# Debugger.net
KiCad netlist of a schematic drawn in Altium Designer
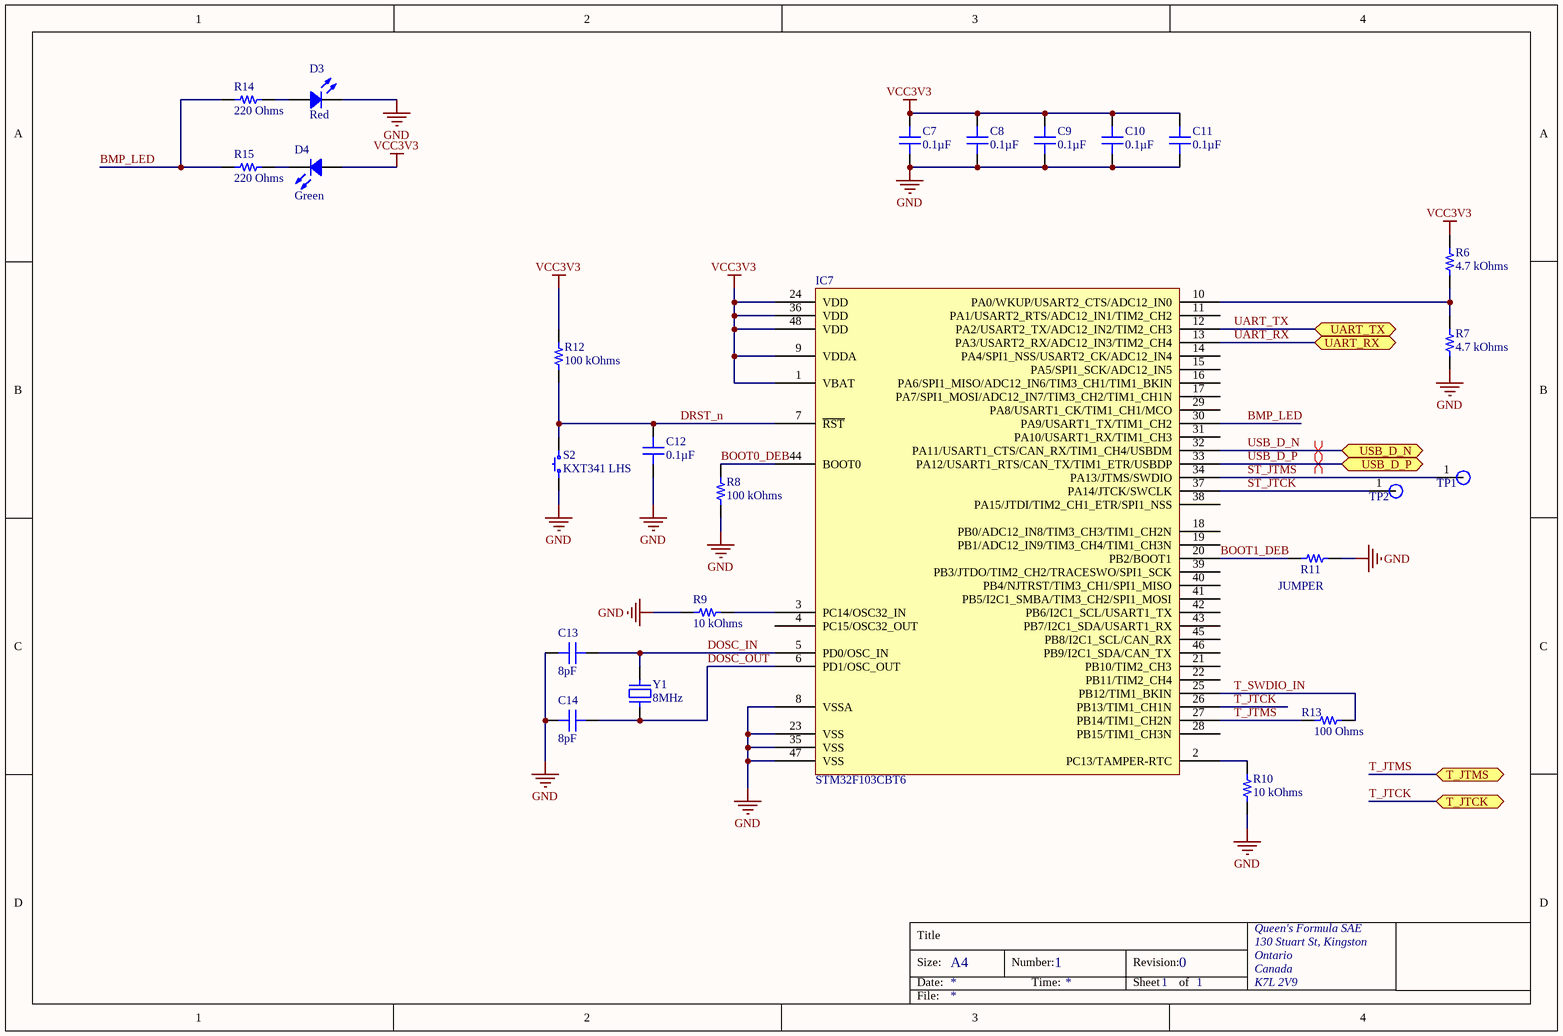
[diagram p0: Debugger.SchDoc]

(export (version "E")
  (design (tool "Eeschema 10.0.6"))
  (components
    (comp (ref "C7")
      (value "0.1µF")
      (footprint "CAP 0201_0603")
      (description "CAP CER 0.1UF 16V X5R 0201")
      (fields (field (name "PART NUMBER") "EMK063BJ104KP-F") (field (name "MANUFACTURER") "Taiyo Yuden"))
      (libsource (lib "Celestial") (part "Capacitor"))
    )
    (comp (ref "C8")
      (value "0.1µF")
      (footprint "CAP 0201_0603")
      (description "CAP CER 0.1UF 16V X5R 0201")
      (fields (field (name "PART NUMBER") "EMK063BJ104KP-F") (field (name "MANUFACTURER") "Taiyo Yuden"))
      (libsource (lib "Celestial") (part "Capacitor"))
    )
    (comp (ref "C9")
      (value "0.1µF")
      (footprint "CAP 0201_0603")
      (description "CAP CER 0.1UF 16V X5R 0201")
      (fields (field (name "PART NUMBER") "EMK063BJ104KP-F") (field (name "MANUFACTURER") "Taiyo Yuden"))
      (libsource (lib "Celestial") (part "Capacitor"))
    )
    (comp (ref "C10")
      (value "0.1µF")
      (footprint "CAP 0201_0603")
      (description "CAP CER 0.1UF 16V X5R 0201")
      (fields (field (name "PART NUMBER") "EMK063BJ104KP-F") (field (name "MANUFACTURER") "Taiyo Yuden"))
      (libsource (lib "Celestial") (part "Capacitor"))
    )
    (comp (ref "C11")
      (value "0.1µF")
      (footprint "CAP 0201_0603")
      (description "CAP CER 0.1UF 16V X5R 0201")
      (fields (field (name "PART NUMBER") "EMK063BJ104KP-F") (field (name "MANUFACTURER") "Taiyo Yuden"))
      (libsource (lib "Celestial") (part "Capacitor"))
    )
    (comp (ref "C12")
      (value "0.1µF")
      (footprint "CAP 0201_0603")
      (description "CAP CER 0.1UF 16V X5R 0201")
      (fields (field (name "PART NUMBER") "EMK063BJ104KP-F") (field (name "MANUFACTURER") "Taiyo Yuden"))
      (libsource (lib "Celestial") (part "Capacitor"))
    )
    (comp (ref "C13")
      (value "8pF")
      (footprint "CAP 0402_1005")
      (description "CAP CER 8PF 50V NP0 0402")
      (fields
        (field (name "PART NUMBER") "C1005NP01H080D050BA")
        (field (name "MANUFACTURER") "TDK Corporation")
      )
      (libsource (lib "Celestial") (part "Capacitor"))
    )
    (comp (ref "C14")
      (value "8pF")
      (footprint "CAP 0402_1005")
      (description "CAP CER 8PF 50V NP0 0402")
      (fields
        (field (name "PART NUMBER") "C1005NP01H080D050BA")
        (field (name "MANUFACTURER") "TDK Corporation")
      )
      (libsource (lib "Celestial") (part "Capacitor"))
    )
    (comp (ref "D3")
      (value "Red")
      (footprint "LED 0402_1005 RED")
      (description "LED RED CLEAR CHIP SMD")
      (fields (field (name "PART NUMBER") "APG1005SEC/E-T") (field (name "MANUFACTURER") "Kingbright"))
      (libsource (lib "Celestial") (part "LED"))
    )
    (comp (ref "D4")
      (value "Green")
      (footprint "LED 0402_1005 GREEN")
      (description "LED GREEN CLEAR 2SMD")
      (fields (field (name "PART NUMBER") "APHHS1005LCGCK") (field (name "MANUFACTURER") "Kingbright"))
      (libsource (lib "Celestial") (part "LED"))
    )
    (comp (ref "IC7")
      (value "STM32F103CBT6")
      (footprint "ST LQFP-48 7X7MM")
      (description "IC MCU 32BIT 128KB FLASH 48LQFP")
      (fields (field (name "MANUFACTURER") "STMicroelectronics"))
      (libsource (lib "Celestial") (part "ST STM32F103 48PIN"))
    )
    (comp (ref "R6")
      (value "4.7 kOhms")
      (footprint "RES 0402_1005")
      (description "RES SMD 4.7K OHM 1% 1/16W 0402")
      (fields (field (name "PART NUMBER") "AC0402FR-074K7L") (field (name "MANUFACTURER") "Yageo"))
      (libsource (lib "Celestial") (part "Resistor"))
    )
    (comp (ref "R7")
      (value "4.7 kOhms")
      (footprint "RES 0402_1005")
      (description "RES SMD 4.7K OHM 1% 1/16W 0402")
      (fields (field (name "PART NUMBER") "AC0402FR-074K7L") (field (name "MANUFACTURER") "Yageo"))
      (libsource (lib "Celestial") (part "Resistor"))
    )
    (comp (ref "R8")
      (value "100 kOhms")
      (footprint "RES 0402_1005")
      (description "RES SMD 100K OHM 1% 1/16W 0402")
      (fields (field (name "PART NUMBER") "AC0402FR-07100KL") (field (name "MANUFACTURER") "Yageo"))
      (libsource (lib "Celestial") (part "Resistor"))
    )
    (comp (ref "R9")
      (value "10 kOhms")
      (footprint "RES 0402_1005")
      (description "RES SMD 10K OHM 1% 1/16W 0402")
      (fields (field (name "PART NUMBER") "AC0402FR-0710KL") (field (name "MANUFACTURER") "Yageo"))
      (libsource (lib "Celestial") (part "Resistor"))
    )
    (comp (ref "R10")
      (value "10 kOhms")
      (footprint "RES 0402_1005")
      (description "RES SMD 10K OHM 1% 1/16W 0402")
      (fields (field (name "PART NUMBER") "AC0402FR-0710KL") (field (name "MANUFACTURER") "Yageo"))
      (libsource (lib "Celestial") (part "Resistor"))
    )
    (comp (ref "R11")
      (value "JUMPER")
      (footprint "RES 0402_1005")
      (description "0402 JUMPER ON TAPE AND REEL")
      (fields (field (name "PART NUMBER") "5113") (field (name "MANUFACTURER") "Keystone Electronics"))
      (libsource (lib "Celestial") (part "Resistor"))
    )
    (comp (ref "R12")
      (value "100 kOhms")
      (footprint "RES 0201_0603")
      (description "RES SMD 100K OHM 1% 1/20W 0201")
      (fields
        (field (name "PART NUMBER") "CRG0201F100K")
        (field (name "MANUFACTURER") "TE Connectivity Passive Product")
      )
      (libsource (lib "Celestial") (part "Resistor"))
    )
    (comp (ref "R13")
      (value "100 Ohms")
      (footprint "RES 0201_0603")
      (description "RES SMD 100 OHM 1% 1/20W 0201")
      (fields (field (name "PART NUMBER") "CRCW0201100RFKED") (field (name "MANUFACTURER") "Vishay Dale"))
      (libsource (lib "Celestial") (part "Resistor"))
    )
    (comp (ref "R14")
      (value "220 Ohms")
      (footprint "RES 0201_0603")
      (description "RES 220 OHM 1% 1/20W 0201")
      (fields
        (field (name "PART NUMBER") "RK73H1HTTC2200F")
        (field (name "MANUFACTURER") "KOA Speer Electronics, Inc.")
      )
      (libsource (lib "Celestial") (part "Resistor"))
    )
    (comp (ref "R15")
      (value "220 Ohms")
      (footprint "RES 0201_0603")
      (description "RES 220 OHM 1% 1/20W 0201")
      (fields
        (field (name "PART NUMBER") "RK73H1HTTC2200F")
        (field (name "MANUFACTURER") "KOA Speer Electronics, Inc.")
      )
      (libsource (lib "Celestial") (part "Resistor"))
    )
    (comp (ref "S2")
      (value "KXT341 LHS")
      (footprint "C&K KXT3")
      (description "SWITCH TACTILE SPST-NO 0.02A 15V")
      (fields (field (name "MANUFACTURER") "C&K"))
      (libsource (lib "Celestial") (part "SPST-NO 2 PIN"))
    )
    (comp (ref "TP1") (value "Test Point") (footprint "ethan:TP1") (libsource (lib "ethan") (part "TP1")))
    (comp (ref "TP2") (value "Test Point") (footprint "ethan:TP1") (libsource (lib "ethan") (part "TP1")))
    (comp (ref "Y1")
      (value "8MHz")
      (footprint "NDK NX3225GD")
      (description "CRYSTAL 8.0000MHZ 8PF SMD")
      (fields
        (field (name "PART NUMBER") "NX3225GD-8MHZ-STD-CRA-3")
        (field (name "MANUFACTURER") "NDK America, Inc.")
      )
      (libsource (lib "Celestial") (part "NDK NX3225GD"))
    )
  )
  (nets
    (net (code "1") (name "/BMP_LED") (class "Default")
      (node (ref "IC7") (pin "30") (pinfunction "PA9/USART1_TX/TIM1_CH2_30") (pintype "passive"))
      (node (ref "R14") (pin "2") (pinfunction "2_2") (pintype "passive"))
      (node (ref "R15") (pin "2") (pinfunction "2_2") (pintype "passive"))
    )
    (net (code "2") (name "/BOOT0_DEB") (class "Default")
      (node (ref "IC7") (pin "44") (pinfunction "BOOT0_44") (pintype "passive"))
      (node (ref "R8") (pin "2") (pinfunction "2_2") (pintype "passive"))
    )
    (net (code "3") (name "/BOOT1_DEB") (class "Default")
      (node (ref "IC7") (pin "20") (pinfunction "PB2/BOOT1_20") (pintype "passive"))
      (node (ref "R11") (pin "2") (pinfunction "2_2") (pintype "passive"))
    )
    (net (code "4") (name "/DOSC_IN") (class "Default")
      (node (ref "C13") (pin "2") (pinfunction "2_2") (pintype "passive"))
      (node (ref "IC7") (pin "5") (pinfunction "PD0/OSC_IN_5") (pintype "passive"))
      (node (ref "Y1") (pin "2") (pinfunction "2_2") (pintype "passive"))
    )
    (net (code "5") (name "/DOSC_OUT") (class "Default")
      (node (ref "C14") (pin "2") (pinfunction "2_2") (pintype "passive"))
      (node (ref "IC7") (pin "6") (pinfunction "PD1/OSC_OUT_6") (pintype "passive"))
      (node (ref "Y1") (pin "1") (pinfunction "1_1") (pintype "passive"))
    )
    (net (code "6") (name "/DRST_n") (class "Default")
      (node (ref "C12") (pin "2") (pinfunction "2_2") (pintype "passive"))
      (node (ref "IC7") (pin "7") (pinfunction "~{RST}_7") (pintype "passive"))
      (node (ref "R12") (pin "1") (pinfunction "1_1") (pintype "passive"))
      (node (ref "S2") (pin "2") (pinfunction "2_2") (pintype "passive"))
    )
    (net (code "7") (name "/ST_JTCK") (class "Default")
      (node (ref "IC7") (pin "37") (pinfunction "PA14/JTCK/SWCLK_37") (pintype "passive"))
      (node (ref "TP2") (pin "1") (pinfunction "1_1") (pintype "passive"))
    )
    (net (code "8") (name "/ST_JTMS") (class "Default")
      (node (ref "IC7") (pin "34") (pinfunction "PA13/JTMS/SWDIO_34") (pintype "passive"))
      (node (ref "TP1") (pin "1") (pinfunction "1_1") (pintype "passive"))
    )
    (net (code "9") (name "/T_JTCK") (class "Default")
      (node (ref "IC7") (pin "26") (pinfunction "PB13/TIM1_CH1N_26") (pintype "passive"))
    )
    (net (code "10") (name "/T_JTMS") (class "Default")
      (node (ref "IC7") (pin "27") (pinfunction "PB14/TIM1_CH2N_27") (pintype "passive"))
      (node (ref "R13") (pin "1") (pinfunction "1_1") (pintype "passive"))
    )
    (net (code "11") (name "/T_SWDIO_IN") (class "Default")
      (node (ref "IC7") (pin "25") (pinfunction "PB12/TIM1_BKIN_25") (pintype "passive"))
      (node (ref "R13") (pin "2") (pinfunction "2_2") (pintype "passive"))
    )
    (net (code "12") (name "/UART_RX") (class "Default")
      (node (ref "IC7") (pin "13") (pinfunction "PA3/USART2_RX/ADC12_IN3/TIM2_CH4_13") (pintype "passive"))
    )
    (net (code "13") (name "/UART_TX") (class "Default")
      (node (ref "IC7") (pin "12") (pinfunction "PA2/USART2_TX/ADC12_IN2/TIM2_CH3_12") (pintype "passive"))
    )
    (net (code "14") (name "/USB_D_N") (class "Default")
      (node (ref "IC7") (pin "32") (pinfunction "PA11/USART1_CTS/CAN_RX/TIM1_CH4/USBDM_32") (pintype "passive"))
    )
    (net (code "15") (name "/USB_D_P") (class "Default")
      (node (ref "IC7") (pin "33") (pinfunction "PA12/USART1_RTS/CAN_TX/TIM1_ETR/USBDP_33") (pintype "passive"))
    )
    (net (code "16") (name "GND") (class "Default")
      (node (ref "C10") (pin "1") (pinfunction "1_1") (pintype "passive"))
      (node (ref "C11") (pin "1") (pinfunction "1_1") (pintype "passive"))
      (node (ref "C12") (pin "1") (pinfunction "1_1") (pintype "passive"))
      (node (ref "C13") (pin "1") (pinfunction "1_1") (pintype "passive"))
      (node (ref "C14") (pin "1") (pinfunction "1_1") (pintype "passive"))
      (node (ref "C7") (pin "1") (pinfunction "1_1") (pintype "passive"))
      (node (ref "C8") (pin "1") (pinfunction "1_1") (pintype "passive"))
      (node (ref "C9") (pin "1") (pinfunction "1_1") (pintype "passive"))
      (node (ref "D3") (pin "2") (pinfunction "2_2") (pintype "passive"))
      (node (ref "IC7") (pin "23") (pinfunction "VSS_23") (pintype "passive"))
      (node (ref "IC7") (pin "35") (pinfunction "VSS_35") (pintype "passive"))
      (node (ref "IC7") (pin "47") (pinfunction "VSS_47") (pintype "passive"))
      (node (ref "IC7") (pin "8") (pinfunction "VSSA_8") (pintype "passive"))
      (node (ref "R10") (pin "1") (pinfunction "1_1") (pintype "passive"))
      (node (ref "R11") (pin "1") (pinfunction "1_1") (pintype "passive"))
      (node (ref "R7") (pin "1") (pinfunction "1_1") (pintype "passive"))
      (node (ref "R8") (pin "1") (pinfunction "1_1") (pintype "passive"))
      (node (ref "R9") (pin "2") (pinfunction "2_2") (pintype "passive"))
      (node (ref "S2") (pin "1") (pinfunction "1_1") (pintype "passive"))
    )
    (net (code "17") (name "Net-(D3-Pad1)") (class "Default")
      (node (ref "D3") (pin "1") (pinfunction "1_1") (pintype "passive"))
      (node (ref "R14") (pin "1") (pinfunction "1_1") (pintype "passive"))
    )
    (net (code "18") (name "Net-(D4-Pad2)") (class "Default")
      (node (ref "D4") (pin "2") (pinfunction "2_2") (pintype "passive"))
      (node (ref "R15") (pin "1") (pinfunction "1_1") (pintype "passive"))
    )
    (net (code "19") (name "Net-(IC7-PA0{slash}WKUP{slash}USART2_CTS{slash}ADC12_IN0)") (class "Default")
      (node (ref "IC7") (pin "10") (pinfunction "PA0/WKUP/USART2_CTS/ADC12_IN0_10") (pintype "passive"))
      (node (ref "R6") (pin "1") (pinfunction "1_1") (pintype "passive"))
      (node (ref "R7") (pin "2") (pinfunction "2_2") (pintype "passive"))
    )
    (net (code "20") (name "Net-(IC7-PC13{slash}TAMPER-RTC)") (class "Default")
      (node (ref "IC7") (pin "2") (pinfunction "PC13/TAMPER-RTC_2") (pintype "passive"))
      (node (ref "R10") (pin "2") (pinfunction "2_2") (pintype "passive"))
    )
    (net (code "21") (name "Net-(IC7-PC14{slash}OSC32_IN)") (class "Default")
      (node (ref "IC7") (pin "3") (pinfunction "PC14/OSC32_IN_3") (pintype "passive"))
      (node (ref "R9") (pin "1") (pinfunction "1_1") (pintype "passive"))
    )
    (net (code "22") (name "VCC3V3") (class "Default")
      (node (ref "C10") (pin "2") (pinfunction "2_2") (pintype "passive"))
      (node (ref "C11") (pin "2") (pinfunction "2_2") (pintype "passive"))
      (node (ref "C7") (pin "2") (pinfunction "2_2") (pintype "passive"))
      (node (ref "C8") (pin "2") (pinfunction "2_2") (pintype "passive"))
      (node (ref "C9") (pin "2") (pinfunction "2_2") (pintype "passive"))
      (node (ref "D4") (pin "1") (pinfunction "1_1") (pintype "passive"))
      (node (ref "IC7") (pin "1") (pinfunction "VBAT_1") (pintype "passive"))
      (node (ref "IC7") (pin "24") (pinfunction "VDD_24") (pintype "passive"))
      (node (ref "IC7") (pin "36") (pinfunction "VDD_36") (pintype "passive"))
      (node (ref "IC7") (pin "48") (pinfunction "VDD_48") (pintype "passive"))
      (node (ref "IC7") (pin "9") (pinfunction "VDDA_9") (pintype "passive"))
      (node (ref "R12") (pin "2") (pinfunction "2_2") (pintype "passive"))
      (node (ref "R6") (pin "2") (pinfunction "2_2") (pintype "passive"))
    )
    (net (code "23") (name "unconnected-(IC7-PA1{slash}USART2_RTS{slash}ADC12_IN1{slash}TIM2_CH2-Pad11)") (class "Default")
      (node (ref "IC7") (pin "11") (pinfunction "PA1/USART2_RTS/ADC12_IN1/TIM2_CH2_11") (pintype "passive"))
    )
    (net (code "24") (name "unconnected-(IC7-PA4{slash}SPI1_NSS{slash}USART2_CK{slash}ADC12_IN4-Pad14)") (class "Default")
      (node (ref "IC7") (pin "14") (pinfunction "PA4/SPI1_NSS/USART2_CK/ADC12_IN4_14") (pintype "passive"))
    )
    (net (code "25") (name "unconnected-(IC7-PA5{slash}SPI1_SCK{slash}ADC12_IN5-Pad15)") (class "Default")
      (node (ref "IC7") (pin "15") (pinfunction "PA5/SPI1_SCK/ADC12_IN5_15") (pintype "passive"))
    )
    (net (code "26") (name "unconnected-(IC7-PA6{slash}SPI1_MISO{slash}ADC12_IN6{slash}TIM3_CH1{slash}TIM1_BKIN-Pad16)") (class "Default")
      (node (ref "IC7") (pin "16") (pinfunction "PA6/SPI1_MISO/ADC12_IN6/TIM3_CH1/TIM1_BKIN_16") (pintype "passive"))
    )
    (net (code "27") (name "unconnected-(IC7-PA7{slash}SPI1_MOSI{slash}ADC12_IN7{slash}TIM3_CH2{slash}TIM1_CH1N-Pad17)") (class "Default")
      (node (ref "IC7") (pin "17") (pinfunction "PA7/SPI1_MOSI/ADC12_IN7/TIM3_CH2/TIM1_CH1N_17") (pintype "passive"))
    )
    (net (code "28") (name "unconnected-(IC7-PA8{slash}USART1_CK{slash}TIM1_CH1{slash}MCO-Pad29)") (class "Default")
      (node (ref "IC7") (pin "29") (pinfunction "PA8/USART1_CK/TIM1_CH1/MCO_29") (pintype "passive"))
    )
    (net (code "29") (name "unconnected-(IC7-PA10{slash}USART1_RX{slash}TIM1_CH3-Pad31)") (class "Default")
      (node (ref "IC7") (pin "31") (pinfunction "PA10/USART1_RX/TIM1_CH3_31") (pintype "passive"))
    )
    (net (code "30") (name "unconnected-(IC7-PA15{slash}JTDI{slash}TIM2_CH1_ETR{slash}SPI1_NSS-Pad38)") (class "Default")
      (node (ref "IC7") (pin "38") (pinfunction "PA15/JTDI/TIM2_CH1_ETR/SPI1_NSS_38") (pintype "passive"))
    )
    (net (code "31") (name "unconnected-(IC7-PB0{slash}ADC12_IN8{slash}TIM3_CH3{slash}TIM1_CH2N-Pad18)") (class "Default")
      (node (ref "IC7") (pin "18") (pinfunction "PB0/ADC12_IN8/TIM3_CH3/TIM1_CH2N_18") (pintype "passive"))
    )
    (net (code "32") (name "unconnected-(IC7-PB1{slash}ADC12_IN9{slash}TIM3_CH4{slash}TIM1_CH3N-Pad19)") (class "Default")
      (node (ref "IC7") (pin "19") (pinfunction "PB1/ADC12_IN9/TIM3_CH4/TIM1_CH3N_19") (pintype "passive"))
    )
    (net (code "33") (name "unconnected-(IC7-PB3{slash}JTDO{slash}TIM2_CH2{slash}TRACESWO{slash}SPI1_SCK-Pad39)") (class "Default")
      (node (ref "IC7") (pin "39") (pinfunction "PB3/JTDO/TIM2_CH2/TRACESWO/SPI1_SCK_39") (pintype "passive"))
    )
    (net (code "34") (name "unconnected-(IC7-PB4{slash}NJTRST{slash}TIM3_CH1{slash}SPI1_MISO-Pad40)") (class "Default")
      (node (ref "IC7") (pin "40") (pinfunction "PB4/NJTRST/TIM3_CH1/SPI1_MISO_40") (pintype "passive"))
    )
    (net (code "35") (name "unconnected-(IC7-PB5{slash}I2C1_SMBA{slash}TIM3_CH2{slash}SPI1_MOSI-Pad41)") (class "Default")
      (node (ref "IC7") (pin "41") (pinfunction "PB5/I2C1_SMBA/TIM3_CH2/SPI1_MOSI_41") (pintype "passive"))
    )
    (net (code "36") (name "unconnected-(IC7-PB6{slash}I2C1_SCL{slash}USART1_TX-Pad42)") (class "Default")
      (node (ref "IC7") (pin "42") (pinfunction "PB6/I2C1_SCL/USART1_TX_42") (pintype "passive"))
    )
    (net (code "37") (name "unconnected-(IC7-PB7{slash}I2C1_SDA{slash}USART1_RX-Pad43)") (class "Default")
      (node (ref "IC7") (pin "43") (pinfunction "PB7/I2C1_SDA/USART1_RX_43") (pintype "passive"))
    )
    (net (code "38") (name "unconnected-(IC7-PB8{slash}I2C1_SCL{slash}CAN_RX-Pad45)") (class "Default")
      (node (ref "IC7") (pin "45") (pinfunction "PB8/I2C1_SCL/CAN_RX_45") (pintype "passive"))
    )
    (net (code "39") (name "unconnected-(IC7-PB9{slash}I2C1_SDA{slash}CAN_TX-Pad46)") (class "Default")
      (node (ref "IC7") (pin "46") (pinfunction "PB9/I2C1_SDA/CAN_TX_46") (pintype "passive"))
    )
    (net (code "40") (name "unconnected-(IC7-PB10{slash}TIM2_CH3-Pad21)") (class "Default")
      (node (ref "IC7") (pin "21") (pinfunction "PB10/TIM2_CH3_21") (pintype "passive"))
    )
    (net (code "41") (name "unconnected-(IC7-PB11{slash}TIM2_CH4-Pad22)") (class "Default")
      (node (ref "IC7") (pin "22") (pinfunction "PB11/TIM2_CH4_22") (pintype "passive"))
    )
    (net (code "42") (name "unconnected-(IC7-PB15{slash}TIM1_CH3N-Pad28)") (class "Default")
      (node (ref "IC7") (pin "28") (pinfunction "PB15/TIM1_CH3N_28") (pintype "passive"))
    )
    (net (code "43") (name "unconnected-(IC7-PC15{slash}OSC32_OUT-Pad4)") (class "Default")
      (node (ref "IC7") (pin "4") (pinfunction "PC15/OSC32_OUT_4") (pintype "passive"))
    )
  )
)
